# XOR_Gate.net
KiCad netlist of a schematic drawn in EAGLE
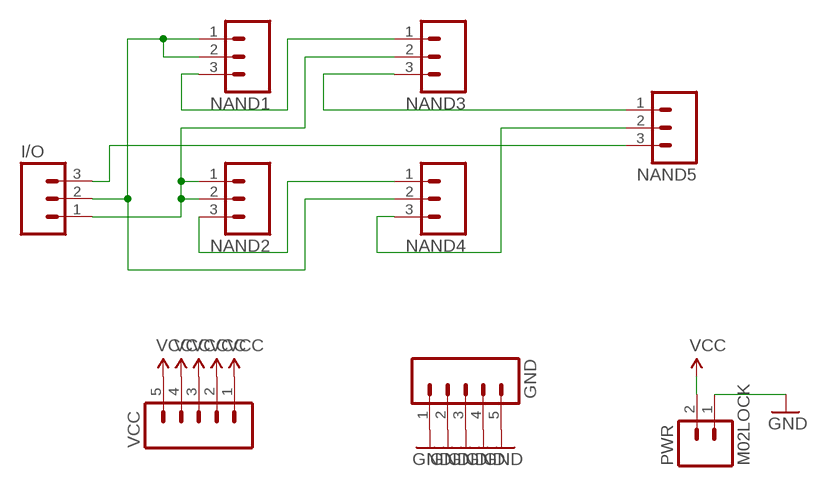
[diagram p0: schematic, sheet 1]

(export (version "E")
  (design (tool "Eeschema 10.0.6"))
  (components
    (comp (ref "GND")
      (value "M05LOCK")
      (footprint "eagle-import:1X05_LOCK")
      (libsource (lib "eagle-import") (part "M05LOCK"))
    )
    (comp (ref "I/O")
      (value "M03LOCK")
      (footprint "eagle-import:1X03_LOCK")
      (libsource (lib "eagle-import") (part "M03LOCK"))
    )
    (comp (ref "NAND1")
      (value "M03LOCK")
      (footprint "eagle-import:1X03_LOCK")
      (libsource (lib "eagle-import") (part "M03LOCK"))
    )
    (comp (ref "NAND2")
      (value "M03LOCK")
      (footprint "eagle-import:1X03_LOCK")
      (libsource (lib "eagle-import") (part "M03LOCK"))
    )
    (comp (ref "NAND3")
      (value "M03LOCK")
      (footprint "eagle-import:1X03_LOCK")
      (libsource (lib "eagle-import") (part "M03LOCK"))
    )
    (comp (ref "NAND4")
      (value "M03LOCK")
      (footprint "eagle-import:1X03_LOCK")
      (libsource (lib "eagle-import") (part "M03LOCK"))
    )
    (comp (ref "NAND5")
      (value "M03LOCK")
      (footprint "eagle-import:1X03_LOCK")
      (libsource (lib "eagle-import") (part "M03LOCK"))
    )
    (comp (ref "PWR")
      (value "M02LOCK")
      (footprint "eagle-import:1X02_LOCK")
      (libsource (lib "eagle-import") (part "M02LOCK"))
    )
    (comp (ref "VCC")
      (value "M05LOCK")
      (footprint "eagle-import:1X05_LOCK")
      (libsource (lib "eagle-import") (part "M05LOCK"))
    )
  )
  (nets
    (net (code "1") (name "GND") (class "Default")
      (node (ref "GND") (pin "1") (pinfunction "1_1") (pintype "passive"))
      (node (ref "GND") (pin "2") (pinfunction "2_2") (pintype "passive"))
      (node (ref "GND") (pin "3") (pinfunction "3_3") (pintype "passive"))
      (node (ref "GND") (pin "4") (pinfunction "4_4") (pintype "passive"))
      (node (ref "GND") (pin "5") (pinfunction "5_5") (pintype "passive"))
      (node (ref "PWR") (pin "1") (pinfunction "1_1") (pintype "passive"))
    )
    (net (code "2") (name "Net-(I/O-Pad1)") (class "Default")
      (node (ref "I/O") (pin "1") (pinfunction "1_1") (pintype "passive"))
      (node (ref "NAND2") (pin "1") (pinfunction "1_1") (pintype "passive"))
      (node (ref "NAND2") (pin "2") (pinfunction "2_2") (pintype "passive"))
      (node (ref "NAND3") (pin "2") (pinfunction "2_2") (pintype "passive"))
    )
    (net (code "3") (name "Net-(I/O-Pad2)") (class "Default")
      (node (ref "I/O") (pin "2") (pinfunction "2_2") (pintype "passive"))
      (node (ref "NAND1") (pin "1") (pinfunction "1_1") (pintype "passive"))
      (node (ref "NAND1") (pin "2") (pinfunction "2_2") (pintype "passive"))
      (node (ref "NAND4") (pin "2") (pinfunction "2_2") (pintype "passive"))
    )
    (net (code "4") (name "Net-(I/O-Pad3)") (class "Default")
      (node (ref "I/O") (pin "3") (pinfunction "3_3") (pintype "passive"))
      (node (ref "NAND5") (pin "3") (pinfunction "3_3") (pintype "passive"))
    )
    (net (code "5") (name "Net-(NAND1-Pad3)") (class "Default")
      (node (ref "NAND1") (pin "3") (pinfunction "3_3") (pintype "passive"))
      (node (ref "NAND3") (pin "1") (pinfunction "1_1") (pintype "passive"))
    )
    (net (code "6") (name "Net-(NAND2-Pad3)") (class "Default")
      (node (ref "NAND2") (pin "3") (pinfunction "3_3") (pintype "passive"))
      (node (ref "NAND4") (pin "1") (pinfunction "1_1") (pintype "passive"))
    )
    (net (code "7") (name "Net-(NAND3-Pad3)") (class "Default")
      (node (ref "NAND3") (pin "3") (pinfunction "3_3") (pintype "passive"))
      (node (ref "NAND5") (pin "1") (pinfunction "1_1") (pintype "passive"))
    )
    (net (code "8") (name "Net-(NAND4-Pad3)") (class "Default")
      (node (ref "NAND4") (pin "3") (pinfunction "3_3") (pintype "passive"))
      (node (ref "NAND5") (pin "2") (pinfunction "2_2") (pintype "passive"))
    )
    (net (code "9") (name "VCC") (class "Default")
      (node (ref "PWR") (pin "2") (pinfunction "2_2") (pintype "passive"))
      (node (ref "VCC") (pin "1") (pinfunction "1_1") (pintype "passive"))
      (node (ref "VCC") (pin "2") (pinfunction "2_2") (pintype "passive"))
      (node (ref "VCC") (pin "3") (pinfunction "3_3") (pintype "passive"))
      (node (ref "VCC") (pin "4") (pinfunction "4_4") (pintype "passive"))
      (node (ref "VCC") (pin "5") (pinfunction "5_5") (pintype "passive"))
    )
  )
)
